# Sockets.net
KiCad netlist of a schematic drawn in Altium Designer
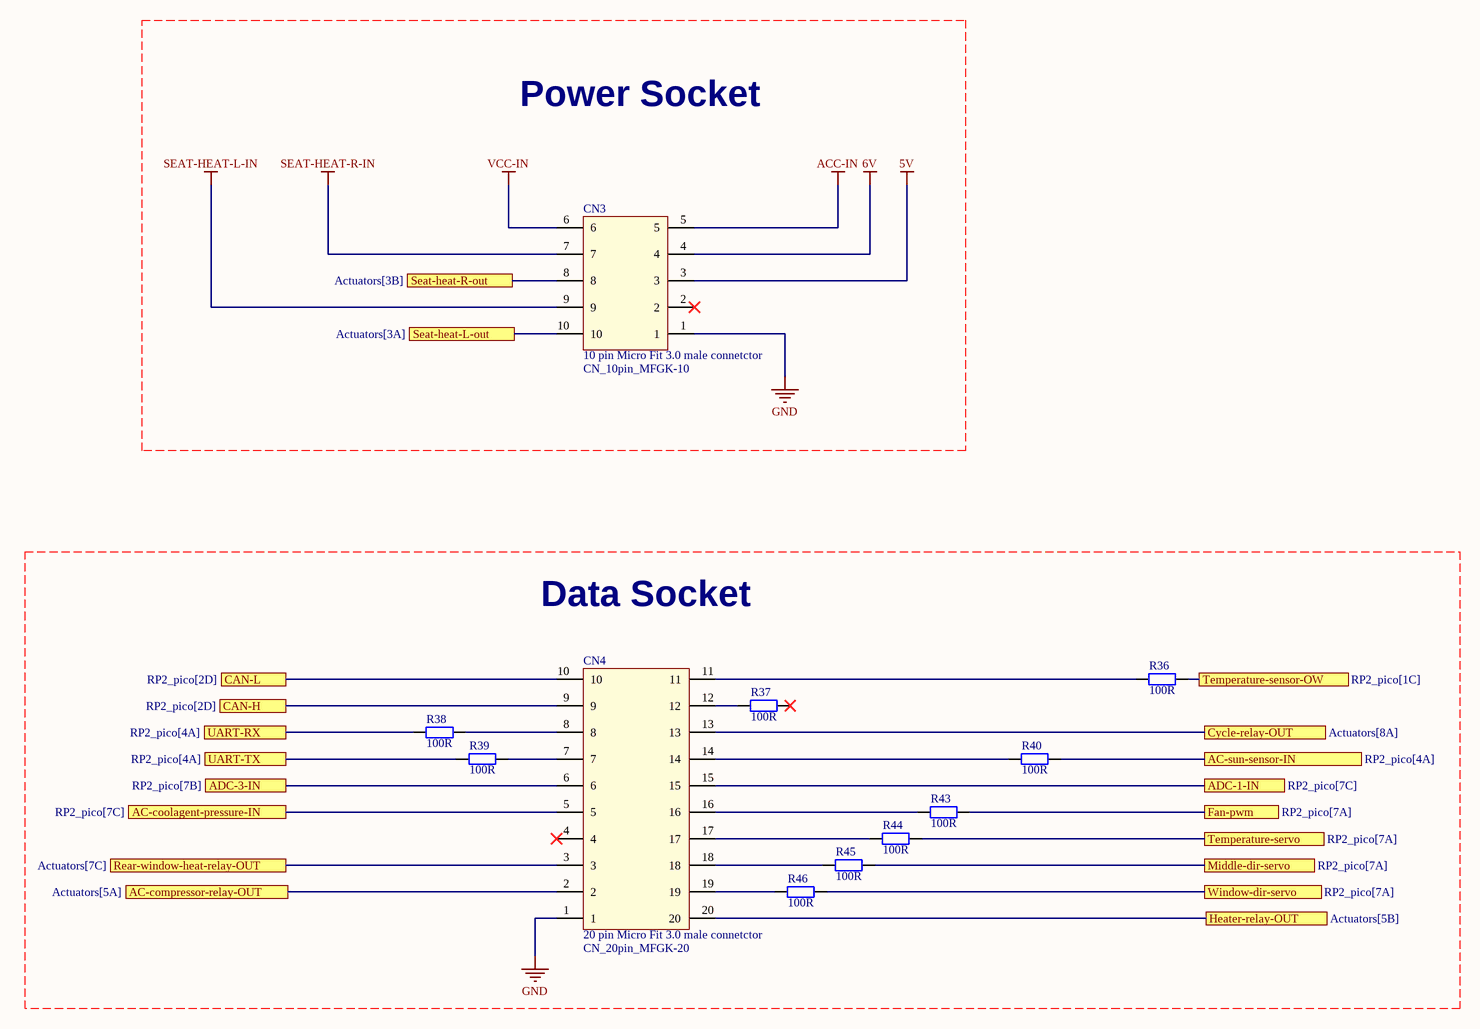
[diagram p0: Sockets.SchDoc]

(export (version "E")
  (design (tool "Eeschema 10.0.6"))
  (components
    (comp (ref "CN3")
      (value "10 pin Micro Fit 3.0 male connetctor")
      (footprint "CN_10pin_MFGK-10")
      (description "Molex, Micro-Fit 3.0, 43045, 10 Way, 2 Row, Right Angle PCB Header")
      (fields (field (name "VALUE1") "CN_10pin_MFGK-10") (field (name "MANUFACTURER") "Molex"))
      (libsource (lib "DSW_Lib") (part "CN_10pin_MFGK-10"))
    )
    (comp (ref "CN4")
      (value "20 pin Micro Fit 3.0 male connetctor")
      (footprint "CN_20pin_MFGK-20")
      (description "Molex, Micro-Fit 3.0, 43045, 20 Way, 2 Row, Right Angle PCB Header")
      (fields (field (name "VALUE1") "CN_20pin_MFGK-20") (field (name "MANUFACTURER") "Molex"))
      (libsource (lib "DSW_Lib") (part "CN_20pin_MFGK-20"))
    )
    (comp (ref "R36")
      (value "RES")
      (footprint "RESC2012X60N")
      (description "RESISTOR, 0805, 100R, 1%, SMD")
      (fields (field (name "VALUE1") "100R") (field (name "MANUFACTURER") "Yageo"))
      (libsource (lib "DSW_Lib") (part "RES"))
    )
    (comp (ref "R37")
      (value "RES")
      (footprint "RESC2012X60N")
      (description "RESISTOR, 0805, 100R, 1%, SMD")
      (fields (field (name "VALUE1") "100R") (field (name "MANUFACTURER") "Yageo"))
      (libsource (lib "DSW_Lib") (part "RES"))
    )
    (comp (ref "R38")
      (value "RES")
      (footprint "RESC2012X60N")
      (description "RESISTOR, 0805, 100R, 1%, SMD")
      (fields (field (name "VALUE1") "100R") (field (name "MANUFACTURER") "Yageo"))
      (libsource (lib "") (part "RES_1"))
    )
    (comp (ref "R39")
      (value "RES")
      (footprint "RESC2012X60N")
      (description "RESISTOR, 0805, 100R, 1%, SMD")
      (fields (field (name "VALUE1") "100R") (field (name "MANUFACTURER") "Yageo"))
      (libsource (lib "") (part "RES_1"))
    )
    (comp (ref "R40")
      (value "RES")
      (footprint "RESC2012X60N")
      (description "RESISTOR, 0805, 100R, 1%, SMD")
      (fields (field (name "VALUE1") "100R") (field (name "MANUFACTURER") "Yageo"))
      (libsource (lib "DSW_Lib") (part "RES"))
    )
    (comp (ref "R43")
      (value "RES")
      (footprint "RESC2012X60N")
      (description "RESISTOR, 0805, 100R, 1%, SMD")
      (fields (field (name "VALUE1") "100R") (field (name "MANUFACTURER") "Yageo"))
      (libsource (lib "DSW_Lib") (part "RES"))
    )
    (comp (ref "R44")
      (value "RES")
      (footprint "RESC2012X60N")
      (description "RESISTOR, 0805, 100R, 1%, SMD")
      (fields (field (name "VALUE1") "100R") (field (name "MANUFACTURER") "Yageo"))
      (libsource (lib "DSW_Lib") (part "RES"))
    )
    (comp (ref "R45")
      (value "RES")
      (footprint "RESC2012X60N")
      (description "RESISTOR, 0805, 100R, 1%, SMD")
      (fields (field (name "VALUE1") "100R") (field (name "MANUFACTURER") "Yageo"))
      (libsource (lib "DSW_Lib") (part "RES"))
    )
    (comp (ref "R46")
      (value "RES")
      (footprint "RESC2012X60N")
      (description "RESISTOR, 0805, 100R, 1%, SMD")
      (fields (field (name "VALUE1") "100R") (field (name "MANUFACTURER") "Yageo"))
      (libsource (lib "DSW_Lib") (part "RES"))
    )
  )
  (nets
    (net (code "1") (name "/AC-compressor-relay-OUT") (class "Default")
      (node (ref "CN4") (pin "2") (pinfunction "2_2") (pintype "passive"))
    )
    (net (code "2") (name "/AC-coolagent-pressure-IN") (class "Default")
      (node (ref "CN4") (pin "5") (pinfunction "5_5") (pintype "passive"))
    )
    (net (code "3") (name "/AC-sun-sensor-IN") (class "Default")
      (node (ref "R40") (pin "2") (pinfunction "2_2") (pintype "passive"))
    )
    (net (code "4") (name "/ADC-1-IN") (class "Default")
      (node (ref "CN4") (pin "15") (pinfunction "15_15") (pintype "passive"))
    )
    (net (code "5") (name "/ADC-3-IN") (class "Default")
      (node (ref "CN4") (pin "6") (pinfunction "6_6") (pintype "passive"))
    )
    (net (code "6") (name "/CAN-H") (class "Default")
      (node (ref "CN4") (pin "9") (pinfunction "9_9") (pintype "passive"))
    )
    (net (code "7") (name "/CAN-L") (class "Default")
      (node (ref "CN4") (pin "10") (pinfunction "10_10") (pintype "passive"))
    )
    (net (code "8") (name "/Cycle-relay-OUT") (class "Default")
      (node (ref "CN4") (pin "13") (pinfunction "13_13") (pintype "passive"))
    )
    (net (code "9") (name "/Fan-pwm") (class "Default")
      (node (ref "R43") (pin "2") (pinfunction "2_2") (pintype "passive"))
    )
    (net (code "10") (name "/Heater-relay-OUT") (class "Default")
      (node (ref "CN4") (pin "20") (pinfunction "20_20") (pintype "passive"))
    )
    (net (code "11") (name "/Middle-dir-servo") (class "Default")
      (node (ref "R45") (pin "2") (pinfunction "2_2") (pintype "passive"))
    )
    (net (code "12") (name "/Rear-window-heat-relay-OUT") (class "Default")
      (node (ref "CN4") (pin "3") (pinfunction "3_3") (pintype "passive"))
    )
    (net (code "13") (name "/Seat-heat-L-out") (class "Default")
      (node (ref "CN3") (pin "10") (pinfunction "10_10") (pintype "passive"))
    )
    (net (code "14") (name "/Seat-heat-R-out") (class "Default")
      (node (ref "CN3") (pin "8") (pinfunction "8_8") (pintype "passive"))
    )
    (net (code "15") (name "/Temperature-sensor-OW") (class "Default")
      (node (ref "R36") (pin "2") (pinfunction "2_2") (pintype "passive"))
    )
    (net (code "16") (name "/Temperature-servo") (class "Default")
      (node (ref "R44") (pin "2") (pinfunction "2_2") (pintype "passive"))
    )
    (net (code "17") (name "/UART-RX") (class "Default")
      (node (ref "R38") (pin "2") (pinfunction "2_2") (pintype "passive"))
    )
    (net (code "18") (name "/UART-TX") (class "Default")
      (node (ref "R39") (pin "2") (pinfunction "2_2") (pintype "passive"))
    )
    (net (code "19") (name "/Window-dir-servo") (class "Default")
      (node (ref "R46") (pin "2") (pinfunction "2_2") (pintype "passive"))
    )
    (net (code "20") (name "5V") (class "Default")
      (node (ref "CN3") (pin "3") (pinfunction "3_3") (pintype "passive"))
    )
    (net (code "21") (name "6V") (class "Default")
      (node (ref "CN3") (pin "4") (pinfunction "4_4") (pintype "passive"))
    )
    (net (code "22") (name "ACC-IN") (class "Default")
      (node (ref "CN3") (pin "5") (pinfunction "5_5") (pintype "passive"))
    )
    (net (code "23") (name "GND") (class "Default")
      (node (ref "CN3") (pin "1") (pinfunction "1_1") (pintype "passive"))
      (node (ref "CN4") (pin "1") (pinfunction "1_1") (pintype "passive"))
    )
    (net (code "24") (name "Net-(CN4-Pad7)") (class "Default")
      (node (ref "CN4") (pin "7") (pinfunction "7_7") (pintype "passive"))
      (node (ref "R39") (pin "1") (pinfunction "1_1") (pintype "passive"))
    )
    (net (code "25") (name "Net-(CN4-Pad8)") (class "Default")
      (node (ref "CN4") (pin "8") (pinfunction "8_8") (pintype "passive"))
      (node (ref "R38") (pin "1") (pinfunction "1_1") (pintype "passive"))
    )
    (net (code "26") (name "Net-(CN4-Pad11)") (class "Default")
      (node (ref "CN4") (pin "11") (pinfunction "11_11") (pintype "passive"))
      (node (ref "R36") (pin "1") (pinfunction "1_1") (pintype "passive"))
    )
    (net (code "27") (name "Net-(CN4-Pad12)") (class "Default")
      (node (ref "CN4") (pin "12") (pinfunction "12_12") (pintype "passive"))
      (node (ref "R37") (pin "1") (pinfunction "1_1") (pintype "passive"))
    )
    (net (code "28") (name "Net-(CN4-Pad14)") (class "Default")
      (node (ref "CN4") (pin "14") (pinfunction "14_14") (pintype "passive"))
      (node (ref "R40") (pin "1") (pinfunction "1_1") (pintype "passive"))
    )
    (net (code "29") (name "Net-(CN4-Pad16)") (class "Default")
      (node (ref "CN4") (pin "16") (pinfunction "16_16") (pintype "passive"))
      (node (ref "R43") (pin "1") (pinfunction "1_1") (pintype "passive"))
    )
    (net (code "30") (name "Net-(CN4-Pad17)") (class "Default")
      (node (ref "CN4") (pin "17") (pinfunction "17_17") (pintype "passive"))
      (node (ref "R44") (pin "1") (pinfunction "1_1") (pintype "passive"))
    )
    (net (code "31") (name "Net-(CN4-Pad18)") (class "Default")
      (node (ref "CN4") (pin "18") (pinfunction "18_18") (pintype "passive"))
      (node (ref "R45") (pin "1") (pinfunction "1_1") (pintype "passive"))
    )
    (net (code "32") (name "Net-(CN4-Pad19)") (class "Default")
      (node (ref "CN4") (pin "19") (pinfunction "19_19") (pintype "passive"))
      (node (ref "R46") (pin "1") (pinfunction "1_1") (pintype "passive"))
    )
    (net (code "33") (name "SEAT-HEAT-L-IN") (class "Default")
      (node (ref "CN3") (pin "9") (pinfunction "9_9") (pintype "passive"))
    )
    (net (code "34") (name "SEAT-HEAT-R-IN") (class "Default")
      (node (ref "CN3") (pin "7") (pinfunction "7_7") (pintype "passive"))
    )
    (net (code "35") (name "VCC-IN") (class "Default")
      (node (ref "CN3") (pin "6") (pinfunction "6_6") (pintype "passive"))
    )
    (net (code "36") (name "unconnected-(CN3-Pad2)") (class "Default")
      (node (ref "CN3") (pin "2") (pinfunction "2_2") (pintype "passive+no_connect"))
    )
    (net (code "37") (name "unconnected-(CN4-Pad4)") (class "Default")
      (node (ref "CN4") (pin "4") (pinfunction "4_4") (pintype "passive+no_connect"))
    )
    (net (code "38") (name "unconnected-(R37-Pad2)") (class "Default")
      (node (ref "R37") (pin "2") (pinfunction "2_2") (pintype "passive+no_connect"))
    )
  )
)
